# ultrasound.net
KiCad netlist of a schematic drawn in EAGLE
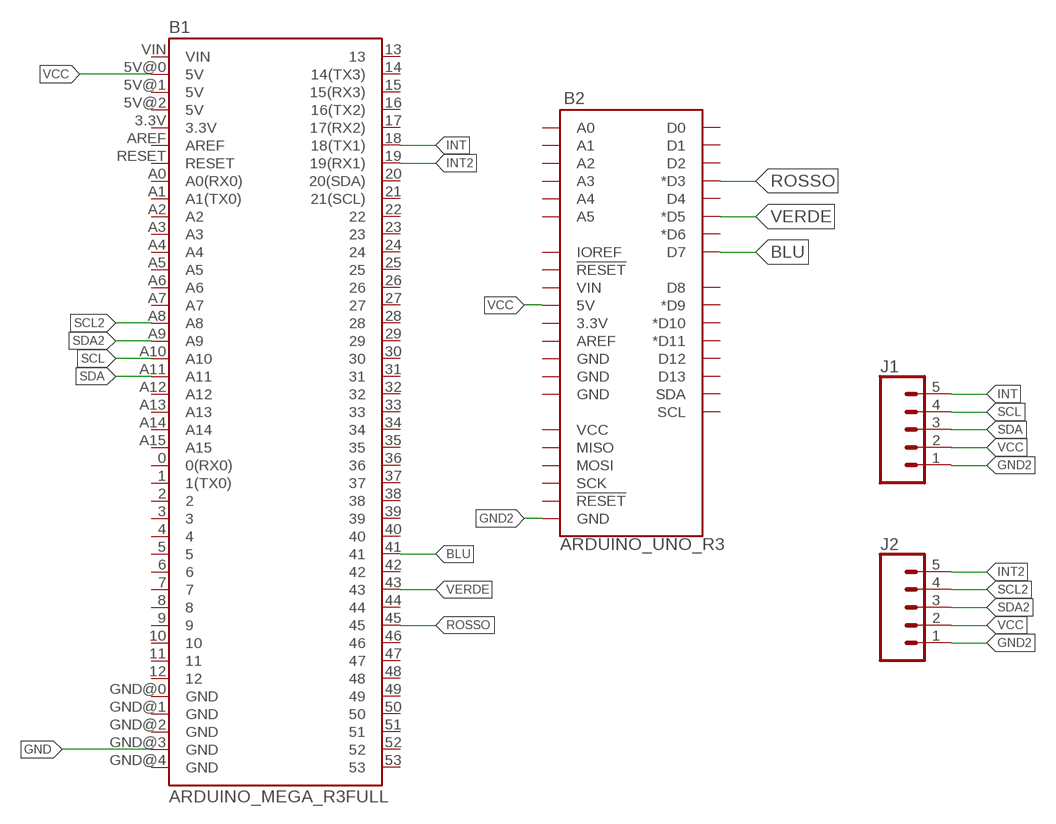
[diagram p0: schematic, sheet 1]

(export (version "E")
  (design (tool "Eeschema 10.0.6"))
  (components
    (comp (ref "B1")
      (value "ARDUINO_MEGA_R3FULL")
      (footprint "eagle-import:ARDUINO_MEGA")
      (libsource (lib "eagle-import") (part "ARDUINO_MEGA_R3FULL"))
    )
    (comp (ref "B2")
      (value "ARDUINO_UNO_R3")
      (footprint "eagle-import:ARDUINO_R3")
      (libsource (lib "eagle-import") (part "ARDUINO_UNO_R3"))
    )
    (comp (ref "J1")
      (value "CONN_05")
      (footprint "eagle-import:1X05")
      (libsource (lib "eagle-import") (part "CONN_05"))
    )
    (comp (ref "J2")
      (value "CONN_05")
      (footprint "eagle-import:1X05")
      (libsource (lib "eagle-import") (part "CONN_05"))
    )
  )
  (nets
    (net (code "1") (name "BLU") (class "Default")
      (node (ref "B1") (pin "41") (pinfunction "41_41") (pintype "bidirectional"))
      (node (ref "B2") (pin "D7") (pinfunction "D7_D7") (pintype "bidirectional"))
    )
    (net (code "2") (name "GND") (class "Default")
      (node (ref "B1") (pin "GND@3") (pinfunction "GND_GND@3") (pintype "bidirectional"))
    )
    (net (code "3") (name "GND2") (class "Default")
      (node (ref "B2") (pin "GND@1") (pinfunction "GND_GND@1") (pintype "bidirectional"))
      (node (ref "J1") (pin "1") (pinfunction "1_1") (pintype "passive"))
      (node (ref "J2") (pin "1") (pinfunction "1_1") (pintype "passive"))
    )
    (net (code "4") (name "INT") (class "Default")
      (node (ref "B1") (pin "18") (pinfunction "18(TX1)_18") (pintype "bidirectional"))
      (node (ref "J1") (pin "5") (pinfunction "5_5") (pintype "passive"))
    )
    (net (code "5") (name "INT2") (class "Default")
      (node (ref "B1") (pin "19") (pinfunction "19(RX1)_19") (pintype "bidirectional"))
      (node (ref "J2") (pin "5") (pinfunction "5_5") (pintype "passive"))
    )
    (net (code "6") (name "ROSSO") (class "Default")
      (node (ref "B1") (pin "45") (pinfunction "45_45") (pintype "bidirectional"))
      (node (ref "B2") (pin "D3") (pinfunction "*D3_D3") (pintype "bidirectional"))
    )
    (net (code "7") (name "SCL") (class "Default")
      (node (ref "B1") (pin "A10") (pinfunction "A10_A10") (pintype "bidirectional"))
      (node (ref "J1") (pin "4") (pinfunction "4_4") (pintype "passive"))
    )
    (net (code "8") (name "SCL2") (class "Default")
      (node (ref "B1") (pin "A8") (pinfunction "A8_A8") (pintype "bidirectional"))
      (node (ref "J2") (pin "4") (pinfunction "4_4") (pintype "passive"))
    )
    (net (code "9") (name "SDA") (class "Default")
      (node (ref "B1") (pin "A11") (pinfunction "A11_A11") (pintype "bidirectional"))
      (node (ref "J1") (pin "3") (pinfunction "3_3") (pintype "passive"))
    )
    (net (code "10") (name "SDA2") (class "Default")
      (node (ref "B1") (pin "A9") (pinfunction "A9_A9") (pintype "bidirectional"))
      (node (ref "J2") (pin "3") (pinfunction "3_3") (pintype "passive"))
    )
    (net (code "11") (name "VCC") (class "Default")
      (node (ref "B1") (pin "5V@0") (pinfunction "5V_5V@0") (pintype "bidirectional"))
      (node (ref "B2") (pin "5V") (pinfunction "5V_5V") (pintype "bidirectional"))
      (node (ref "J1") (pin "2") (pinfunction "2_2") (pintype "passive"))
      (node (ref "J2") (pin "2") (pinfunction "2_2") (pintype "passive"))
    )
    (net (code "12") (name "VERDE") (class "Default")
      (node (ref "B1") (pin "43") (pinfunction "43_43") (pintype "bidirectional"))
      (node (ref "B2") (pin "D5") (pinfunction "*D5_D5") (pintype "bidirectional"))
    )
    (net (code "13") (name "unconnected-(B1-0(RX0)-Pad0)") (class "Default")
      (node (ref "B1") (pin "0") (pinfunction "0(RX0)_0") (pintype "bidirectional"))
    )
    (net (code "14") (name "unconnected-(B1-1(TX0)-Pad1)") (class "Default")
      (node (ref "B1") (pin "1") (pinfunction "1(TX0)_1") (pintype "bidirectional"))
    )
    (net (code "15") (name "unconnected-(B1-5V-Pad5V@1)") (class "Default")
      (node (ref "B1") (pin "5V@1") (pinfunction "5V_5V@1") (pintype "bidirectional"))
    )
    (net (code "16") (name "unconnected-(B1-5V-Pad5V@2)") (class "Default")
      (node (ref "B1") (pin "5V@2") (pinfunction "5V_5V@2") (pintype "bidirectional"))
    )
    (net (code "17") (name "unconnected-(B1-14(TX3)-Pad14)") (class "Default")
      (node (ref "B1") (pin "14") (pinfunction "14(TX3)_14") (pintype "bidirectional"))
    )
    (net (code "18") (name "unconnected-(B1-15(RX3)-Pad15)") (class "Default")
      (node (ref "B1") (pin "15") (pinfunction "15(RX3)_15") (pintype "bidirectional"))
    )
    (net (code "19") (name "unconnected-(B1-16(TX2)-Pad16)") (class "Default")
      (node (ref "B1") (pin "16") (pinfunction "16(TX2)_16") (pintype "bidirectional"))
    )
    (net (code "20") (name "unconnected-(B1-17(RX2)-Pad17)") (class "Default")
      (node (ref "B1") (pin "17") (pinfunction "17(RX2)_17") (pintype "bidirectional"))
    )
    (net (code "21") (name "unconnected-(B1-20(SDA)-Pad20)") (class "Default")
      (node (ref "B1") (pin "20") (pinfunction "20(SDA)_20") (pintype "bidirectional"))
    )
    (net (code "22") (name "unconnected-(B1-21(SCL)-Pad21)") (class "Default")
      (node (ref "B1") (pin "21") (pinfunction "21(SCL)_21") (pintype "bidirectional"))
    )
    (net (code "23") (name "unconnected-(B1-A0(RX0)-PadA0)") (class "Default")
      (node (ref "B1") (pin "A0") (pinfunction "A0(RX0)_A0") (pintype "bidirectional"))
    )
    (net (code "24") (name "unconnected-(B1-A1(TX0)-PadA1)") (class "Default")
      (node (ref "B1") (pin "A1") (pinfunction "A1(TX0)_A1") (pintype "bidirectional"))
    )
    (net (code "25") (name "unconnected-(B1-GND-PadGND@0)") (class "Default")
      (node (ref "B1") (pin "GND@0") (pinfunction "GND_GND@0") (pintype "bidirectional"))
    )
    (net (code "26") (name "unconnected-(B1-GND-PadGND@1)") (class "Default")
      (node (ref "B1") (pin "GND@1") (pinfunction "GND_GND@1") (pintype "bidirectional"))
    )
    (net (code "27") (name "unconnected-(B1-GND-PadGND@2)") (class "Default")
      (node (ref "B1") (pin "GND@2") (pinfunction "GND_GND@2") (pintype "bidirectional"))
    )
    (net (code "28") (name "unconnected-(B1-GND-PadGND@4)") (class "Default")
      (node (ref "B1") (pin "GND@4") (pinfunction "GND_GND@4") (pintype "bidirectional"))
    )
    (net (code "29") (name "unconnected-(B1-Pad2)") (class "Default")
      (node (ref "B1") (pin "2") (pinfunction "2_2") (pintype "bidirectional"))
    )
    (net (code "30") (name "unconnected-(B1-Pad3)") (class "Default")
      (node (ref "B1") (pin "3") (pinfunction "3_3") (pintype "bidirectional"))
    )
    (net (code "31") (name "unconnected-(B1-Pad3.3V)") (class "Default")
      (node (ref "B1") (pin "3.3V") (pinfunction "3.3V_3.3V") (pintype "bidirectional"))
    )
    (net (code "32") (name "unconnected-(B1-Pad4)") (class "Default")
      (node (ref "B1") (pin "4") (pinfunction "4_4") (pintype "bidirectional"))
    )
    (net (code "33") (name "unconnected-(B1-Pad5)") (class "Default")
      (node (ref "B1") (pin "5") (pinfunction "5_5") (pintype "bidirectional"))
    )
    (net (code "34") (name "unconnected-(B1-Pad6)") (class "Default")
      (node (ref "B1") (pin "6") (pinfunction "6_6") (pintype "bidirectional"))
    )
    (net (code "35") (name "unconnected-(B1-Pad7)") (class "Default")
      (node (ref "B1") (pin "7") (pinfunction "7_7") (pintype "bidirectional"))
    )
    (net (code "36") (name "unconnected-(B1-Pad8)") (class "Default")
      (node (ref "B1") (pin "8") (pinfunction "8_8") (pintype "bidirectional"))
    )
    (net (code "37") (name "unconnected-(B1-Pad9)") (class "Default")
      (node (ref "B1") (pin "9") (pinfunction "9_9") (pintype "bidirectional"))
    )
    (net (code "38") (name "unconnected-(B1-Pad10)") (class "Default")
      (node (ref "B1") (pin "10") (pinfunction "10_10") (pintype "bidirectional"))
    )
    (net (code "39") (name "unconnected-(B1-Pad11)") (class "Default")
      (node (ref "B1") (pin "11") (pinfunction "11_11") (pintype "bidirectional"))
    )
    (net (code "40") (name "unconnected-(B1-Pad12)") (class "Default")
      (node (ref "B1") (pin "12") (pinfunction "12_12") (pintype "bidirectional"))
    )
    (net (code "41") (name "unconnected-(B1-Pad13)") (class "Default")
      (node (ref "B1") (pin "13") (pinfunction "13_13") (pintype "bidirectional"))
    )
    (net (code "42") (name "unconnected-(B1-Pad22)") (class "Default")
      (node (ref "B1") (pin "22") (pinfunction "22_22") (pintype "bidirectional"))
    )
    (net (code "43") (name "unconnected-(B1-Pad23)") (class "Default")
      (node (ref "B1") (pin "23") (pinfunction "23_23") (pintype "bidirectional"))
    )
    (net (code "44") (name "unconnected-(B1-Pad24)") (class "Default")
      (node (ref "B1") (pin "24") (pinfunction "24_24") (pintype "bidirectional"))
    )
    (net (code "45") (name "unconnected-(B1-Pad25)") (class "Default")
      (node (ref "B1") (pin "25") (pinfunction "25_25") (pintype "bidirectional"))
    )
    (net (code "46") (name "unconnected-(B1-Pad26)") (class "Default")
      (node (ref "B1") (pin "26") (pinfunction "26_26") (pintype "bidirectional"))
    )
    (net (code "47") (name "unconnected-(B1-Pad27)") (class "Default")
      (node (ref "B1") (pin "27") (pinfunction "27_27") (pintype "bidirectional"))
    )
    (net (code "48") (name "unconnected-(B1-Pad28)") (class "Default")
      (node (ref "B1") (pin "28") (pinfunction "28_28") (pintype "bidirectional"))
    )
    (net (code "49") (name "unconnected-(B1-Pad29)") (class "Default")
      (node (ref "B1") (pin "29") (pinfunction "29_29") (pintype "bidirectional"))
    )
    (net (code "50") (name "unconnected-(B1-Pad30)") (class "Default")
      (node (ref "B1") (pin "30") (pinfunction "30_30") (pintype "bidirectional"))
    )
    (net (code "51") (name "unconnected-(B1-Pad31)") (class "Default")
      (node (ref "B1") (pin "31") (pinfunction "31_31") (pintype "bidirectional"))
    )
    (net (code "52") (name "unconnected-(B1-Pad32)") (class "Default")
      (node (ref "B1") (pin "32") (pinfunction "32_32") (pintype "bidirectional"))
    )
    (net (code "53") (name "unconnected-(B1-Pad33)") (class "Default")
      (node (ref "B1") (pin "33") (pinfunction "33_33") (pintype "bidirectional"))
    )
    (net (code "54") (name "unconnected-(B1-Pad34)") (class "Default")
      (node (ref "B1") (pin "34") (pinfunction "34_34") (pintype "bidirectional"))
    )
    (net (code "55") (name "unconnected-(B1-Pad35)") (class "Default")
      (node (ref "B1") (pin "35") (pinfunction "35_35") (pintype "bidirectional"))
    )
    (net (code "56") (name "unconnected-(B1-Pad36)") (class "Default")
      (node (ref "B1") (pin "36") (pinfunction "36_36") (pintype "bidirectional"))
    )
    (net (code "57") (name "unconnected-(B1-Pad37)") (class "Default")
      (node (ref "B1") (pin "37") (pinfunction "37_37") (pintype "bidirectional"))
    )
    (net (code "58") (name "unconnected-(B1-Pad38)") (class "Default")
      (node (ref "B1") (pin "38") (pinfunction "38_38") (pintype "bidirectional"))
    )
    (net (code "59") (name "unconnected-(B1-Pad39)") (class "Default")
      (node (ref "B1") (pin "39") (pinfunction "39_39") (pintype "bidirectional"))
    )
    (net (code "60") (name "unconnected-(B1-Pad40)") (class "Default")
      (node (ref "B1") (pin "40") (pinfunction "40_40") (pintype "bidirectional"))
    )
    (net (code "61") (name "unconnected-(B1-Pad42)") (class "Default")
      (node (ref "B1") (pin "42") (pinfunction "42_42") (pintype "bidirectional"))
    )
    (net (code "62") (name "unconnected-(B1-Pad44)") (class "Default")
      (node (ref "B1") (pin "44") (pinfunction "44_44") (pintype "bidirectional"))
    )
    (net (code "63") (name "unconnected-(B1-Pad46)") (class "Default")
      (node (ref "B1") (pin "46") (pinfunction "46_46") (pintype "bidirectional"))
    )
    (net (code "64") (name "unconnected-(B1-Pad47)") (class "Default")
      (node (ref "B1") (pin "47") (pinfunction "47_47") (pintype "bidirectional"))
    )
    (net (code "65") (name "unconnected-(B1-Pad48)") (class "Default")
      (node (ref "B1") (pin "48") (pinfunction "48_48") (pintype "bidirectional"))
    )
    (net (code "66") (name "unconnected-(B1-Pad49)") (class "Default")
      (node (ref "B1") (pin "49") (pinfunction "49_49") (pintype "bidirectional"))
    )
    (net (code "67") (name "unconnected-(B1-Pad50)") (class "Default")
      (node (ref "B1") (pin "50") (pinfunction "50_50") (pintype "bidirectional"))
    )
    (net (code "68") (name "unconnected-(B1-Pad51)") (class "Default")
      (node (ref "B1") (pin "51") (pinfunction "51_51") (pintype "bidirectional"))
    )
    (net (code "69") (name "unconnected-(B1-Pad52)") (class "Default")
      (node (ref "B1") (pin "52") (pinfunction "52_52") (pintype "bidirectional"))
    )
    (net (code "70") (name "unconnected-(B1-Pad53)") (class "Default")
      (node (ref "B1") (pin "53") (pinfunction "53_53") (pintype "bidirectional"))
    )
    (net (code "71") (name "unconnected-(B1-PadA2)") (class "Default")
      (node (ref "B1") (pin "A2") (pinfunction "A2_A2") (pintype "bidirectional"))
    )
    (net (code "72") (name "unconnected-(B1-PadA3)") (class "Default")
      (node (ref "B1") (pin "A3") (pinfunction "A3_A3") (pintype "bidirectional"))
    )
    (net (code "73") (name "unconnected-(B1-PadA4)") (class "Default")
      (node (ref "B1") (pin "A4") (pinfunction "A4_A4") (pintype "bidirectional"))
    )
    (net (code "74") (name "unconnected-(B1-PadA5)") (class "Default")
      (node (ref "B1") (pin "A5") (pinfunction "A5_A5") (pintype "bidirectional"))
    )
    (net (code "75") (name "unconnected-(B1-PadA6)") (class "Default")
      (node (ref "B1") (pin "A6") (pinfunction "A6_A6") (pintype "bidirectional"))
    )
    (net (code "76") (name "unconnected-(B1-PadA7)") (class "Default")
      (node (ref "B1") (pin "A7") (pinfunction "A7_A7") (pintype "bidirectional"))
    )
    (net (code "77") (name "unconnected-(B1-PadA12)") (class "Default")
      (node (ref "B1") (pin "A12") (pinfunction "A12_A12") (pintype "bidirectional"))
    )
    (net (code "78") (name "unconnected-(B1-PadA13)") (class "Default")
      (node (ref "B1") (pin "A13") (pinfunction "A13_A13") (pintype "bidirectional"))
    )
    (net (code "79") (name "unconnected-(B1-PadA14)") (class "Default")
      (node (ref "B1") (pin "A14") (pinfunction "A14_A14") (pintype "bidirectional"))
    )
    (net (code "80") (name "unconnected-(B1-PadA15)") (class "Default")
      (node (ref "B1") (pin "A15") (pinfunction "A15_A15") (pintype "bidirectional"))
    )
    (net (code "81") (name "unconnected-(B1-PadAREF)") (class "Default")
      (node (ref "B1") (pin "AREF") (pinfunction "AREF_AREF") (pintype "bidirectional"))
    )
    (net (code "82") (name "unconnected-(B1-PadRESET)") (class "Default")
      (node (ref "B1") (pin "RESET") (pinfunction "RESET_RESET") (pintype "bidirectional"))
    )
    (net (code "83") (name "unconnected-(B1-PadVIN)") (class "Default")
      (node (ref "B1") (pin "VIN") (pinfunction "VIN_VIN") (pintype "bidirectional"))
    )
    (net (code "84") (name "unconnected-(B2-*D6-PadD6)") (class "Default")
      (node (ref "B2") (pin "D6") (pinfunction "*D6_D6") (pintype "bidirectional"))
    )
    (net (code "85") (name "unconnected-(B2-*D9-PadD9)") (class "Default")
      (node (ref "B2") (pin "D9") (pinfunction "*D9_D9") (pintype "bidirectional"))
    )
    (net (code "86") (name "unconnected-(B2-*D10-PadD10)") (class "Default")
      (node (ref "B2") (pin "D10") (pinfunction "*D10_D10") (pintype "bidirectional"))
    )
    (net (code "87") (name "unconnected-(B2-*D11-PadD11)") (class "Default")
      (node (ref "B2") (pin "D11") (pinfunction "*D11_D11") (pintype "bidirectional"))
    )
    (net (code "88") (name "unconnected-(B2-GND-PadGND@2)") (class "Default")
      (node (ref "B2") (pin "GND@2") (pinfunction "GND_GND@2") (pintype "bidirectional"))
    )
    (net (code "89") (name "unconnected-(B2-GND-PadGND@3)") (class "Default")
      (node (ref "B2") (pin "GND@3") (pinfunction "GND_GND@3") (pintype "bidirectional"))
    )
    (net (code "90") (name "unconnected-(B2-GND-PadGND@4)") (class "Default")
      (node (ref "B2") (pin "GND@4") (pinfunction "GND_GND@4") (pintype "bidirectional"))
    )
    (net (code "91") (name "unconnected-(B2-Pad3.3V)") (class "Default")
      (node (ref "B2") (pin "3.3V") (pinfunction "3.3V_3.3V") (pintype "bidirectional"))
    )
    (net (code "92") (name "unconnected-(B2-PadA0)") (class "Default")
      (node (ref "B2") (pin "A0") (pinfunction "A0_A0") (pintype "bidirectional"))
    )
    (net (code "93") (name "unconnected-(B2-PadA1)") (class "Default")
      (node (ref "B2") (pin "A1") (pinfunction "A1_A1") (pintype "bidirectional"))
    )
    (net (code "94") (name "unconnected-(B2-PadA2)") (class "Default")
      (node (ref "B2") (pin "A2") (pinfunction "A2_A2") (pintype "bidirectional"))
    )
    (net (code "95") (name "unconnected-(B2-PadA3)") (class "Default")
      (node (ref "B2") (pin "A3") (pinfunction "A3_A3") (pintype "bidirectional"))
    )
    (net (code "96") (name "unconnected-(B2-PadA4)") (class "Default")
      (node (ref "B2") (pin "A4") (pinfunction "A4_A4") (pintype "bidirectional"))
    )
    (net (code "97") (name "unconnected-(B2-PadA5)") (class "Default")
      (node (ref "B2") (pin "A5") (pinfunction "A5_A5") (pintype "bidirectional"))
    )
    (net (code "98") (name "unconnected-(B2-PadAREF)") (class "Default")
      (node (ref "B2") (pin "AREF") (pinfunction "AREF_AREF") (pintype "bidirectional"))
    )
    (net (code "99") (name "unconnected-(B2-PadD0)") (class "Default")
      (node (ref "B2") (pin "D0") (pinfunction "D0_D0") (pintype "bidirectional"))
    )
    (net (code "100") (name "unconnected-(B2-PadD1)") (class "Default")
      (node (ref "B2") (pin "D1") (pinfunction "D1_D1") (pintype "bidirectional"))
    )
    (net (code "101") (name "unconnected-(B2-PadD2)") (class "Default")
      (node (ref "B2") (pin "D2") (pinfunction "D2_D2") (pintype "bidirectional"))
    )
    (net (code "102") (name "unconnected-(B2-PadD4)") (class "Default")
      (node (ref "B2") (pin "D4") (pinfunction "D4_D4") (pintype "bidirectional"))
    )
    (net (code "103") (name "unconnected-(B2-PadD8)") (class "Default")
      (node (ref "B2") (pin "D8") (pinfunction "D8_D8") (pintype "bidirectional"))
    )
    (net (code "104") (name "unconnected-(B2-PadD12)") (class "Default")
      (node (ref "B2") (pin "D12") (pinfunction "D12_D12") (pintype "bidirectional"))
    )
    (net (code "105") (name "unconnected-(B2-PadD13)") (class "Default")
      (node (ref "B2") (pin "D13") (pinfunction "D13_D13") (pintype "bidirectional"))
    )
    (net (code "106") (name "unconnected-(B2-PadIOREF)") (class "Default")
      (node (ref "B2") (pin "IOREF") (pinfunction "IOREF_IOREF") (pintype "bidirectional"))
    )
    (net (code "107") (name "unconnected-(B2-PadMISO)") (class "Default")
      (node (ref "B2") (pin "MISO") (pinfunction "MISO_MISO") (pintype "bidirectional"))
    )
    (net (code "108") (name "unconnected-(B2-PadMOSI)") (class "Default")
      (node (ref "B2") (pin "MOSI") (pinfunction "MOSI_MOSI") (pintype "bidirectional"))
    )
    (net (code "109") (name "unconnected-(B2-PadSCK)") (class "Default")
      (node (ref "B2") (pin "SCK") (pinfunction "SCK_SCK") (pintype "bidirectional"))
    )
    (net (code "110") (name "unconnected-(B2-PadSCL)") (class "Default")
      (node (ref "B2") (pin "SCL") (pinfunction "SCL_SCL") (pintype "bidirectional"))
    )
    (net (code "111") (name "unconnected-(B2-PadSDA)") (class "Default")
      (node (ref "B2") (pin "SDA") (pinfunction "SDA_SDA") (pintype "bidirectional"))
    )
    (net (code "112") (name "unconnected-(B2-PadVCC)") (class "Default")
      (node (ref "B2") (pin "VCC") (pinfunction "VCC_VCC") (pintype "bidirectional"))
    )
    (net (code "113") (name "unconnected-(B2-PadVIN)") (class "Default")
      (node (ref "B2") (pin "VIN") (pinfunction "VIN_VIN") (pintype "bidirectional"))
    )
    (net (code "114") (name "unconnected-(B2-~{RESET}-PadRESET@1)") (class "Default")
      (node (ref "B2") (pin "RESET@1") (pinfunction "~{RESET}_RESET@1") (pintype "bidirectional"))
    )
    (net (code "115") (name "unconnected-(B2-~{RESET}-PadRESET@2)") (class "Default")
      (node (ref "B2") (pin "RESET@2") (pinfunction "~{RESET}_RESET@2") (pintype "bidirectional"))
    )
  )
)
